# atmosphere2n.net
KiCad netlist of a schematic drawn in EAGLE
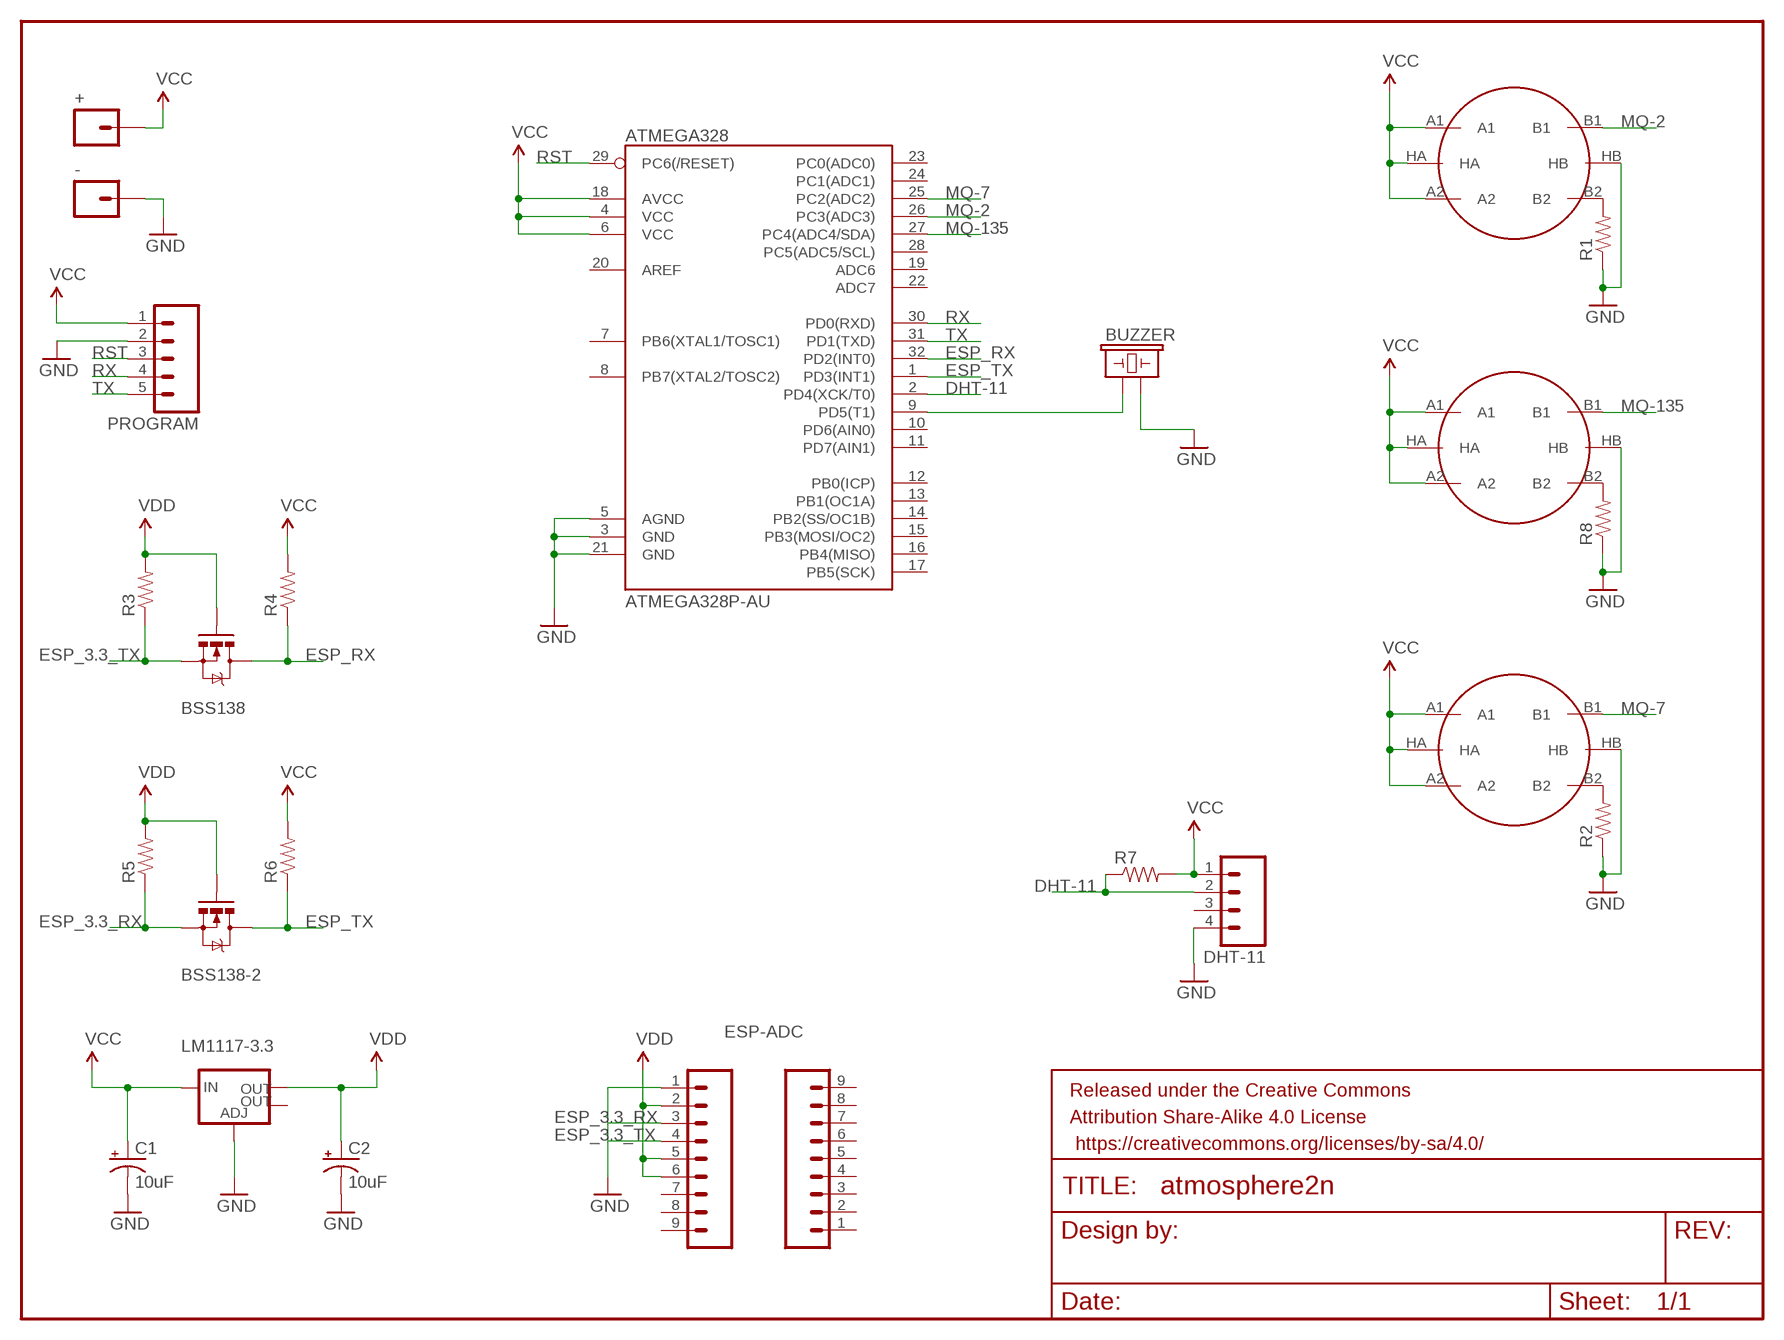
[diagram p0: schematic, sheet 1]

(export (version "E")
  (design (tool "Eeschema 10.0.6"))
  (components
    (comp (ref "+")
      (value "M01SMD")
      (footprint "eagle-import:LUXEON-PAD")
      (libsource (lib "eagle-import") (part "M01SMD"))
    )
    (comp (ref "-")
      (value "M01SMD")
      (footprint "eagle-import:LUXEON-PAD")
      (libsource (lib "eagle-import") (part "M01SMD"))
    )
    (comp (ref "ATMEGA328P-AU")
      (value "ATMEGA328")
      (footprint "eagle-import:TQFP32-08")
      (libsource (lib "eagle-import") (part "ATMEGA328"))
    )
    (comp (ref "BSS138")
      (value "MOSFET-NCHANNELBSS138")
      (footprint "eagle-import:SOT23-3")
      (libsource (lib "eagle-import") (part "MOSFET-NCHANNELBSS138"))
    )
    (comp (ref "BSS138-2")
      (value "MOSFET-NCHANNELBSS138")
      (footprint "eagle-import:SOT23-3")
      (libsource (lib "eagle-import") (part "MOSFET-NCHANNELBSS138"))
    )
    (comp (ref "BUZZER")
      (value "BUZZERNS")
      (footprint "eagle-import:BUZZER-12MM-NS")
      (libsource (lib "eagle-import") (part "BUZZERNS"))
    )
    (comp (ref "C1")
      (value "10uF")
      (footprint "eagle-import:EIA3216")
      (libsource (lib "eagle-import") (part "10UF-16V-10%(TANT)"))
    )
    (comp (ref "C2")
      (value "10uF")
      (footprint "eagle-import:EIA3216")
      (libsource (lib "eagle-import") (part "10UF-16V-10%(TANT)"))
    )
    (comp (ref "DHT-11")
      (value "M04NO_SILK_ALL_ROUND")
      (footprint "eagle-import:1X04_NO_SILK_ALL_ROUND")
      (libsource (lib "eagle-import") (part "M04NO_SILK_ALL_ROUND"))
    )
    (comp (ref "ESP-ADC")
      (value "M09NO_SILK")
      (footprint "eagle-import:1X09_NO_SILK")
      (libsource (lib "eagle-import") (part "M09NO_SILK"))
    )
    (comp (ref "FRAME1")
      (value "FRAME-LETTER")
      (footprint "eagle-import:CREATIVE_COMMONS")
      (libsource (lib "eagle-import") (part "FRAME-LETTER"))
    )
    (comp (ref "J5")
      (value "M09NO_SILK")
      (footprint "eagle-import:1X09_NO_SILK")
      (libsource (lib "eagle-import") (part "M09NO_SILK"))
    )
    (comp (ref "LM1117-3.3")
      (value "V_REG_LM1117SOT223")
      (footprint "eagle-import:SOT223")
      (libsource (lib "eagle-import") (part "V_REG_LM1117SOT223"))
    )
    (comp (ref "PROGRAM")
      (value "M05NO_SILK")
      (footprint "eagle-import:1X05_NO_SILK")
      (libsource (lib "eagle-import") (part "M05NO_SILK"))
    )
    (comp (ref "R1")
      (value "RESISTOR0805-RES")
      (footprint "eagle-import:0805")
      (libsource (lib "eagle-import") (part "RESISTOR0805-RES"))
    )
    (comp (ref "R2")
      (value "RESISTOR0805-RES")
      (footprint "eagle-import:0805")
      (libsource (lib "eagle-import") (part "RESISTOR0805-RES"))
    )
    (comp (ref "R3")
      (value "RESISTOR0805-RES")
      (footprint "eagle-import:0805")
      (libsource (lib "eagle-import") (part "RESISTOR0805-RES"))
    )
    (comp (ref "R4")
      (value "RESISTOR0805-RES")
      (footprint "eagle-import:0805")
      (libsource (lib "eagle-import") (part "RESISTOR0805-RES"))
    )
    (comp (ref "R5")
      (value "RESISTOR0805-RES")
      (footprint "eagle-import:0805")
      (libsource (lib "eagle-import") (part "RESISTOR0805-RES"))
    )
    (comp (ref "R6")
      (value "RESISTOR0805-RES")
      (footprint "eagle-import:0805")
      (libsource (lib "eagle-import") (part "RESISTOR0805-RES"))
    )
    (comp (ref "R7")
      (value "RESISTOR0805-RES")
      (footprint "eagle-import:0805")
      (libsource (lib "eagle-import") (part "RESISTOR0805-RES"))
    )
    (comp (ref "R8")
      (value "RESISTOR0805-RES")
      (footprint "eagle-import:0805")
      (libsource (lib "eagle-import") (part "RESISTOR0805-RES"))
    )
    (comp (ref "U$1")
      (value "METHANE_SENSOR")
      (footprint "eagle-import:MQ-3")
      (libsource (lib "eagle-import") (part "METHANE_SENSOR"))
    )
    (comp (ref "U$2")
      (value "METHANE_SENSOR")
      (footprint "eagle-import:MQ-3")
      (libsource (lib "eagle-import") (part "METHANE_SENSOR"))
    )
    (comp (ref "U$3")
      (value "METHANE_SENSOR")
      (footprint "eagle-import:MQ-3")
      (libsource (lib "eagle-import") (part "METHANE_SENSOR"))
    )
  )
  (nets
    (net (code "1") (name "/DHT-11") (class "Default")
      (node (ref "ATMEGA328P-AU") (pin "2") (pinfunction "PD4(XCK/T0)_2") (pintype "bidirectional"))
      (node (ref "DHT-11") (pin "2") (pinfunction "2_2") (pintype "passive"))
      (node (ref "R7") (pin "1") (pinfunction "1_1") (pintype "passive"))
    )
    (net (code "2") (name "/ESP_3.3_RX") (class "Default")
      (node (ref "BSS138-2") (pin "2") (pinfunction "S_2") (pintype "passive"))
      (node (ref "ESP-ADC") (pin "3") (pinfunction "3_3") (pintype "passive"))
      (node (ref "R5") (pin "1") (pinfunction "1_1") (pintype "passive"))
    )
    (net (code "3") (name "/ESP_3.3_TX") (class "Default")
      (node (ref "BSS138") (pin "2") (pinfunction "S_2") (pintype "passive"))
      (node (ref "ESP-ADC") (pin "4") (pinfunction "4_4") (pintype "passive"))
      (node (ref "R3") (pin "1") (pinfunction "1_1") (pintype "passive"))
    )
    (net (code "4") (name "/ESP_RX") (class "Default")
      (node (ref "ATMEGA328P-AU") (pin "32") (pinfunction "PD2(INT0)_32") (pintype "bidirectional"))
      (node (ref "BSS138") (pin "3") (pinfunction "D_3") (pintype "passive"))
      (node (ref "R4") (pin "1") (pinfunction "1_1") (pintype "passive"))
    )
    (net (code "5") (name "/ESP_TX") (class "Default")
      (node (ref "ATMEGA328P-AU") (pin "1") (pinfunction "PD3(INT1)_1") (pintype "bidirectional"))
      (node (ref "BSS138-2") (pin "3") (pinfunction "D_3") (pintype "passive"))
      (node (ref "R6") (pin "1") (pinfunction "1_1") (pintype "passive"))
    )
    (net (code "6") (name "/MQ-2") (class "Default")
      (node (ref "ATMEGA328P-AU") (pin "26") (pinfunction "PC3(ADC3)_26") (pintype "bidirectional"))
      (node (ref "U$1") (pin "B1") (pinfunction "B1_B1") (pintype "bidirectional"))
    )
    (net (code "7") (name "/MQ-7") (class "Default")
      (node (ref "ATMEGA328P-AU") (pin "25") (pinfunction "PC2(ADC2)_25") (pintype "bidirectional"))
      (node (ref "U$3") (pin "B1") (pinfunction "B1_B1") (pintype "bidirectional"))
    )
    (net (code "8") (name "/MQ-135") (class "Default")
      (node (ref "ATMEGA328P-AU") (pin "27") (pinfunction "PC4(ADC4/SDA)_27") (pintype "bidirectional"))
      (node (ref "U$2") (pin "B1") (pinfunction "B1_B1") (pintype "bidirectional"))
    )
    (net (code "9") (name "/RST") (class "Default")
      (node (ref "ATMEGA328P-AU") (pin "29") (pinfunction "PC6(/RESET)_29") (pintype "bidirectional"))
      (node (ref "PROGRAM") (pin "3") (pinfunction "3_3") (pintype "passive"))
    )
    (net (code "10") (name "/RX") (class "Default")
      (node (ref "ATMEGA328P-AU") (pin "30") (pinfunction "PD0(RXD)_30") (pintype "bidirectional"))
      (node (ref "PROGRAM") (pin "4") (pinfunction "4_4") (pintype "passive"))
    )
    (net (code "11") (name "/TX") (class "Default")
      (node (ref "ATMEGA328P-AU") (pin "31") (pinfunction "PD1(TXD)_31") (pintype "bidirectional"))
      (node (ref "PROGRAM") (pin "5") (pinfunction "5_5") (pintype "passive"))
    )
    (net (code "12") (name "GND") (class "Default")
      (node (ref "-") (pin "P$1") (pinfunction "1_P$1") (pintype "passive"))
      (node (ref "ATMEGA328P-AU") (pin "21") (pinfunction "GND_21") (pintype "bidirectional"))
      (node (ref "ATMEGA328P-AU") (pin "3") (pinfunction "GND_3") (pintype "bidirectional"))
      (node (ref "ATMEGA328P-AU") (pin "5") (pinfunction "AGND_5") (pintype "bidirectional"))
      (node (ref "BUZZER") (pin "-") (pinfunction "2_-") (pintype "passive"))
      (node (ref "C1") (pin "C") (pinfunction "-_C") (pintype "passive"))
      (node (ref "C2") (pin "C") (pinfunction "-_C") (pintype "passive"))
      (node (ref "DHT-11") (pin "4") (pinfunction "4_4") (pintype "passive"))
      (node (ref "ESP-ADC") (pin "1") (pinfunction "1_1") (pintype "passive"))
      (node (ref "LM1117-3.3") (pin "1") (pinfunction "ADJ_1") (pintype "input"))
      (node (ref "PROGRAM") (pin "2") (pinfunction "2_2") (pintype "passive"))
      (node (ref "R1") (pin "1") (pinfunction "1_1") (pintype "passive"))
      (node (ref "R2") (pin "1") (pinfunction "1_1") (pintype "passive"))
      (node (ref "R8") (pin "1") (pinfunction "1_1") (pintype "passive"))
      (node (ref "U$1") (pin "HB") (pinfunction "HB_HB") (pintype "bidirectional"))
      (node (ref "U$2") (pin "HB") (pinfunction "HB_HB") (pintype "bidirectional"))
      (node (ref "U$3") (pin "HB") (pinfunction "HB_HB") (pintype "bidirectional"))
    )
    (net (code "13") (name "Net-(ATMEGA328P-AU-PD5(T1))") (class "Default")
      (node (ref "ATMEGA328P-AU") (pin "9") (pinfunction "PD5(T1)_9") (pintype "bidirectional"))
      (node (ref "BUZZER") (pin "+") (pinfunction "1_+") (pintype "passive"))
    )
    (net (code "14") (name "Net-(R1-Pad2)") (class "Default")
      (node (ref "R1") (pin "2") (pinfunction "2_2") (pintype "passive"))
      (node (ref "U$1") (pin "B2") (pinfunction "B2_B2") (pintype "bidirectional"))
    )
    (net (code "15") (name "Net-(R2-Pad2)") (class "Default")
      (node (ref "R2") (pin "2") (pinfunction "2_2") (pintype "passive"))
      (node (ref "U$3") (pin "B2") (pinfunction "B2_B2") (pintype "bidirectional"))
    )
    (net (code "16") (name "Net-(R8-Pad2)") (class "Default")
      (node (ref "R8") (pin "2") (pinfunction "2_2") (pintype "passive"))
      (node (ref "U$2") (pin "B2") (pinfunction "B2_B2") (pintype "bidirectional"))
    )
    (net (code "17") (name "VCC") (class "Default")
      (node (ref "+") (pin "P$1") (pinfunction "1_P$1") (pintype "passive"))
      (node (ref "ATMEGA328P-AU") (pin "18") (pinfunction "AVCC_18") (pintype "bidirectional"))
      (node (ref "ATMEGA328P-AU") (pin "4") (pinfunction "VCC_4") (pintype "bidirectional"))
      (node (ref "ATMEGA328P-AU") (pin "6") (pinfunction "VCC_6") (pintype "bidirectional"))
      (node (ref "C1") (pin "A") (pinfunction "+_A") (pintype "passive"))
      (node (ref "DHT-11") (pin "1") (pinfunction "1_1") (pintype "passive"))
      (node (ref "LM1117-3.3") (pin "3") (pinfunction "IN_3") (pintype "input"))
      (node (ref "PROGRAM") (pin "1") (pinfunction "1_1") (pintype "passive"))
      (node (ref "R4") (pin "2") (pinfunction "2_2") (pintype "passive"))
      (node (ref "R6") (pin "2") (pinfunction "2_2") (pintype "passive"))
      (node (ref "R7") (pin "2") (pinfunction "2_2") (pintype "passive"))
      (node (ref "U$1") (pin "A1") (pinfunction "A1_A1") (pintype "bidirectional"))
      (node (ref "U$1") (pin "A2") (pinfunction "A2_A2") (pintype "bidirectional"))
      (node (ref "U$1") (pin "HA") (pinfunction "HA_HA") (pintype "bidirectional"))
      (node (ref "U$2") (pin "A1") (pinfunction "A1_A1") (pintype "bidirectional"))
      (node (ref "U$2") (pin "A2") (pinfunction "A2_A2") (pintype "bidirectional"))
      (node (ref "U$2") (pin "HA") (pinfunction "HA_HA") (pintype "bidirectional"))
      (node (ref "U$3") (pin "A1") (pinfunction "A1_A1") (pintype "bidirectional"))
      (node (ref "U$3") (pin "A2") (pinfunction "A2_A2") (pintype "bidirectional"))
      (node (ref "U$3") (pin "HA") (pinfunction "HA_HA") (pintype "bidirectional"))
    )
    (net (code "18") (name "VDD") (class "Default")
      (node (ref "BSS138") (pin "1") (pinfunction "G_1") (pintype "passive"))
      (node (ref "BSS138-2") (pin "1") (pinfunction "G_1") (pintype "passive"))
      (node (ref "C2") (pin "A") (pinfunction "+_A") (pintype "passive"))
      (node (ref "ESP-ADC") (pin "2") (pinfunction "2_2") (pintype "passive"))
      (node (ref "ESP-ADC") (pin "5") (pinfunction "5_5") (pintype "passive"))
      (node (ref "ESP-ADC") (pin "6") (pinfunction "6_6") (pintype "passive"))
      (node (ref "LM1117-3.3") (pin "2") (pinfunction "OUT_2") (pintype "output"))
      (node (ref "R3") (pin "2") (pinfunction "2_2") (pintype "passive"))
      (node (ref "R5") (pin "2") (pinfunction "2_2") (pintype "passive"))
    )
    (net (code "19") (name "unconnected-(ATMEGA328P-AU-ADC6-Pad19)") (class "Default")
      (node (ref "ATMEGA328P-AU") (pin "19") (pinfunction "ADC6_19") (pintype "bidirectional"))
    )
    (net (code "20") (name "unconnected-(ATMEGA328P-AU-ADC7-Pad22)") (class "Default")
      (node (ref "ATMEGA328P-AU") (pin "22") (pinfunction "ADC7_22") (pintype "bidirectional"))
    )
    (net (code "21") (name "unconnected-(ATMEGA328P-AU-AREF-Pad20)") (class "Default")
      (node (ref "ATMEGA328P-AU") (pin "20") (pinfunction "AREF_20") (pintype "bidirectional"))
    )
    (net (code "22") (name "unconnected-(ATMEGA328P-AU-PB0(ICP)-Pad12)") (class "Default")
      (node (ref "ATMEGA328P-AU") (pin "12") (pinfunction "PB0(ICP)_12") (pintype "bidirectional"))
    )
    (net (code "23") (name "unconnected-(ATMEGA328P-AU-PB1(OC1A)-Pad13)") (class "Default")
      (node (ref "ATMEGA328P-AU") (pin "13") (pinfunction "PB1(OC1A)_13") (pintype "bidirectional"))
    )
    (net (code "24") (name "unconnected-(ATMEGA328P-AU-PB2(SS{slash}OC1B)-Pad14)") (class "Default")
      (node (ref "ATMEGA328P-AU") (pin "14") (pinfunction "PB2(SS/OC1B)_14") (pintype "bidirectional"))
    )
    (net (code "25") (name "unconnected-(ATMEGA328P-AU-PB3(MOSI{slash}OC2)-Pad15)") (class "Default")
      (node (ref "ATMEGA328P-AU") (pin "15") (pinfunction "PB3(MOSI/OC2)_15") (pintype "bidirectional"))
    )
    (net (code "26") (name "unconnected-(ATMEGA328P-AU-PB4(MISO)-Pad16)") (class "Default")
      (node (ref "ATMEGA328P-AU") (pin "16") (pinfunction "PB4(MISO)_16") (pintype "bidirectional"))
    )
    (net (code "27") (name "unconnected-(ATMEGA328P-AU-PB5(SCK)-Pad17)") (class "Default")
      (node (ref "ATMEGA328P-AU") (pin "17") (pinfunction "PB5(SCK)_17") (pintype "bidirectional"))
    )
    (net (code "28") (name "unconnected-(ATMEGA328P-AU-PB6(XTAL1{slash}TOSC1)-Pad7)") (class "Default")
      (node (ref "ATMEGA328P-AU") (pin "7") (pinfunction "PB6(XTAL1/TOSC1)_7") (pintype "bidirectional"))
    )
    (net (code "29") (name "unconnected-(ATMEGA328P-AU-PB7(XTAL2{slash}TOSC2)-Pad8)") (class "Default")
      (node (ref "ATMEGA328P-AU") (pin "8") (pinfunction "PB7(XTAL2/TOSC2)_8") (pintype "bidirectional"))
    )
    (net (code "30") (name "unconnected-(ATMEGA328P-AU-PC0(ADC0)-Pad23)") (class "Default")
      (node (ref "ATMEGA328P-AU") (pin "23") (pinfunction "PC0(ADC0)_23") (pintype "bidirectional"))
    )
    (net (code "31") (name "unconnected-(ATMEGA328P-AU-PC1(ADC1)-Pad24)") (class "Default")
      (node (ref "ATMEGA328P-AU") (pin "24") (pinfunction "PC1(ADC1)_24") (pintype "bidirectional"))
    )
    (net (code "32") (name "unconnected-(ATMEGA328P-AU-PC5(ADC5{slash}SCL)-Pad28)") (class "Default")
      (node (ref "ATMEGA328P-AU") (pin "28") (pinfunction "PC5(ADC5/SCL)_28") (pintype "bidirectional"))
    )
    (net (code "33") (name "unconnected-(ATMEGA328P-AU-PD6(AIN0)-Pad10)") (class "Default")
      (node (ref "ATMEGA328P-AU") (pin "10") (pinfunction "PD6(AIN0)_10") (pintype "bidirectional"))
    )
    (net (code "34") (name "unconnected-(ATMEGA328P-AU-PD7(AIN1)-Pad11)") (class "Default")
      (node (ref "ATMEGA328P-AU") (pin "11") (pinfunction "PD7(AIN1)_11") (pintype "bidirectional"))
    )
    (net (code "35") (name "unconnected-(DHT-11-Pad3)") (class "Default")
      (node (ref "DHT-11") (pin "3") (pinfunction "3_3") (pintype "passive"))
    )
    (net (code "36") (name "unconnected-(ESP-ADC-Pad7)") (class "Default")
      (node (ref "ESP-ADC") (pin "7") (pinfunction "7_7") (pintype "passive"))
    )
    (net (code "37") (name "unconnected-(ESP-ADC-Pad8)") (class "Default")
      (node (ref "ESP-ADC") (pin "8") (pinfunction "8_8") (pintype "passive"))
    )
    (net (code "38") (name "unconnected-(ESP-ADC-Pad9)") (class "Default")
      (node (ref "ESP-ADC") (pin "9") (pinfunction "9_9") (pintype "passive"))
    )
    (net (code "39") (name "unconnected-(J5-Pad1)") (class "Default")
      (node (ref "J5") (pin "1") (pinfunction "1_1") (pintype "passive"))
    )
    (net (code "40") (name "unconnected-(J5-Pad2)") (class "Default")
      (node (ref "J5") (pin "2") (pinfunction "2_2") (pintype "passive"))
    )
    (net (code "41") (name "unconnected-(J5-Pad3)") (class "Default")
      (node (ref "J5") (pin "3") (pinfunction "3_3") (pintype "passive"))
    )
    (net (code "42") (name "unconnected-(J5-Pad4)") (class "Default")
      (node (ref "J5") (pin "4") (pinfunction "4_4") (pintype "passive"))
    )
    (net (code "43") (name "unconnected-(J5-Pad5)") (class "Default")
      (node (ref "J5") (pin "5") (pinfunction "5_5") (pintype "passive"))
    )
    (net (code "44") (name "unconnected-(J5-Pad6)") (class "Default")
      (node (ref "J5") (pin "6") (pinfunction "6_6") (pintype "passive"))
    )
    (net (code "45") (name "unconnected-(J5-Pad7)") (class "Default")
      (node (ref "J5") (pin "7") (pinfunction "7_7") (pintype "passive"))
    )
    (net (code "46") (name "unconnected-(J5-Pad8)") (class "Default")
      (node (ref "J5") (pin "8") (pinfunction "8_8") (pintype "passive"))
    )
    (net (code "47") (name "unconnected-(J5-Pad9)") (class "Default")
      (node (ref "J5") (pin "9") (pinfunction "9_9") (pintype "passive"))
    )
    (net (code "48") (name "unconnected-(LM1117-3.3-OUT-Pad4)") (class "Default")
      (node (ref "LM1117-3.3") (pin "4") (pinfunction "OUT_4") (pintype "output"))
    )
  )
)
